# Sensor_Board.net
KiCad netlist of a schematic drawn in EAGLE
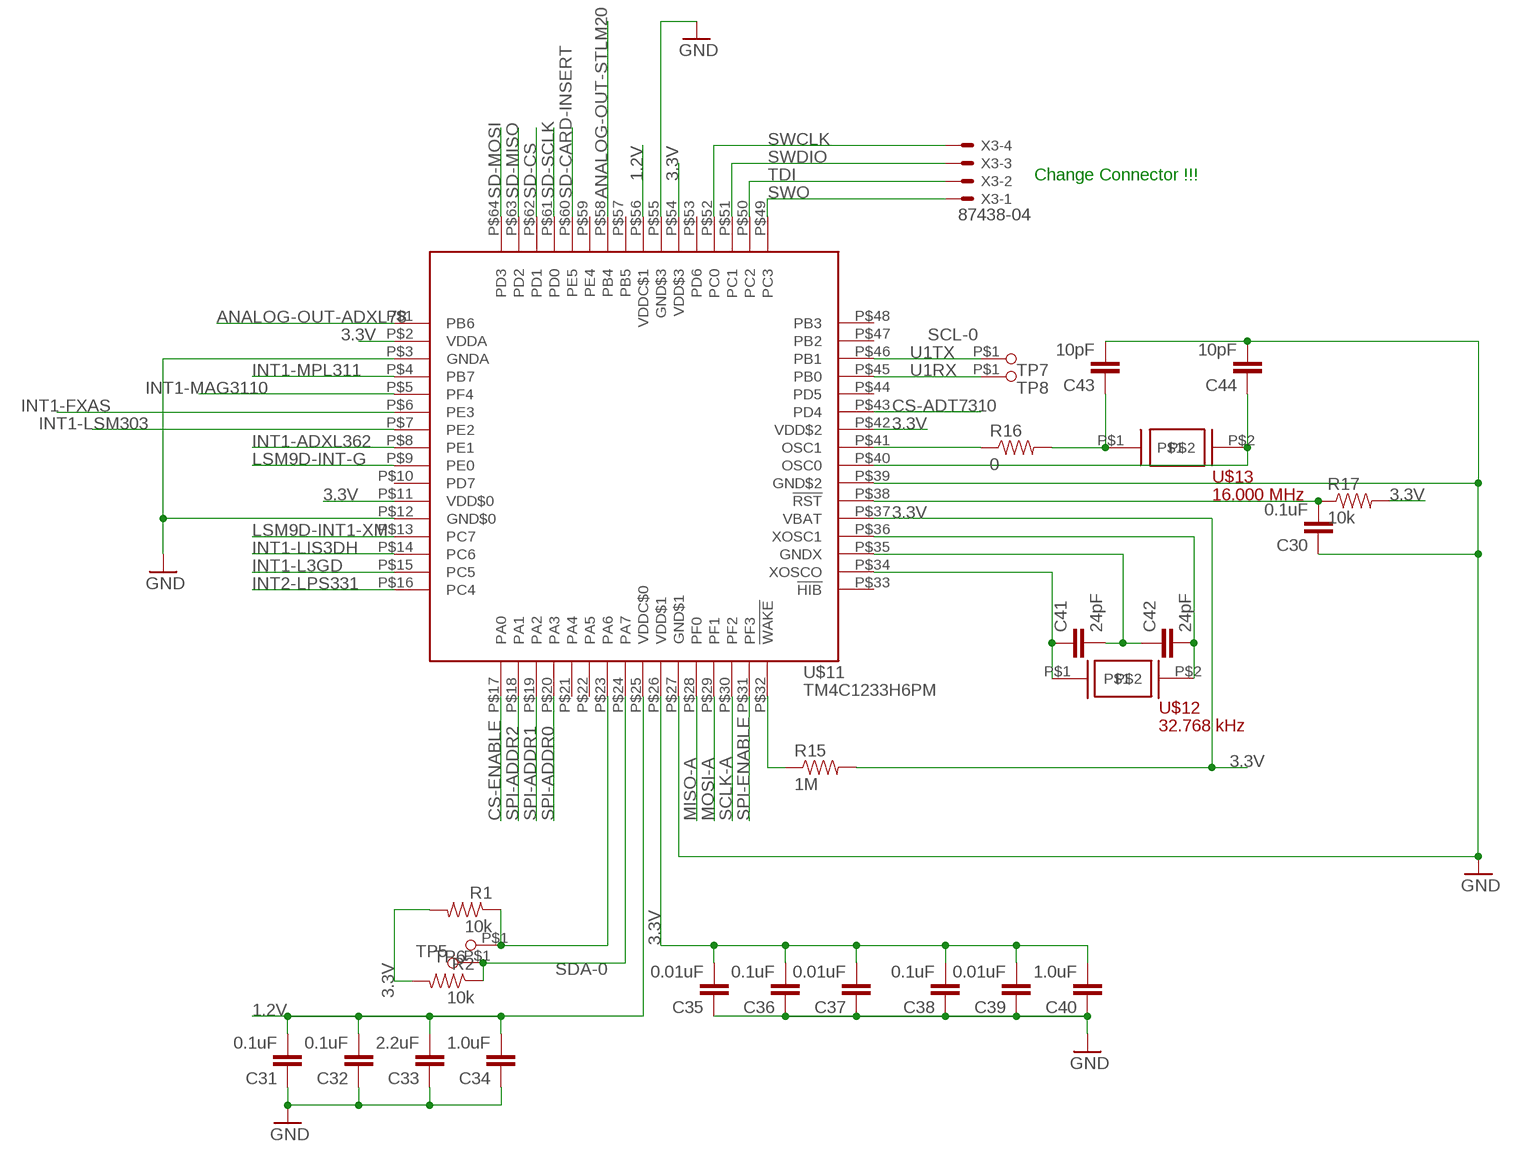
[diagram p0: schematic, sheet 1]
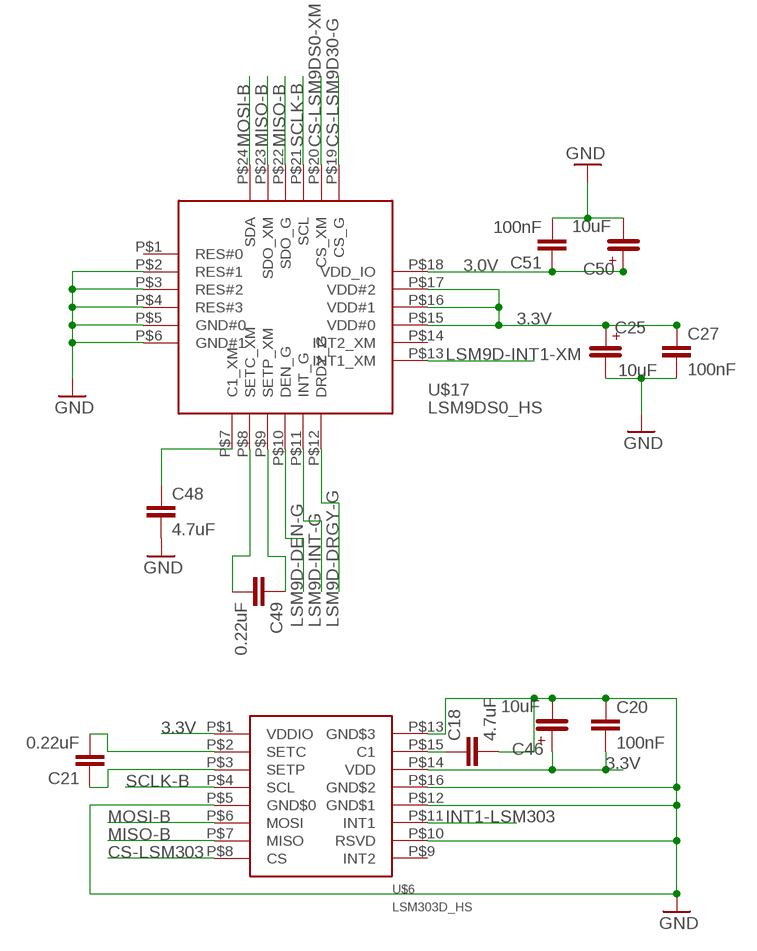
[diagram p1: schematic, sheet 2]
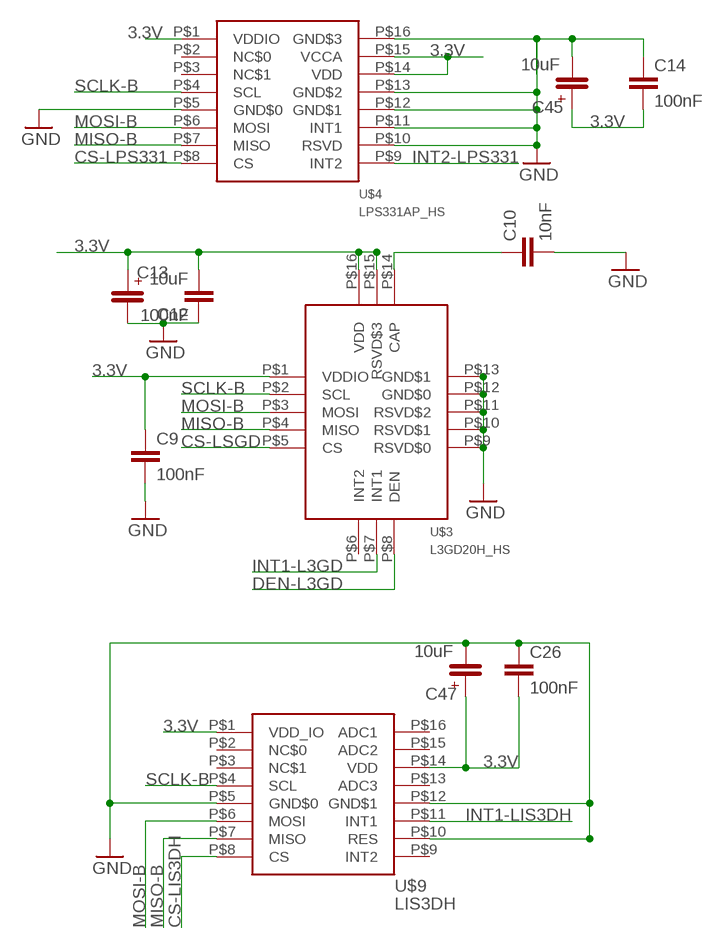
[diagram p2: schematic, sheet 3]
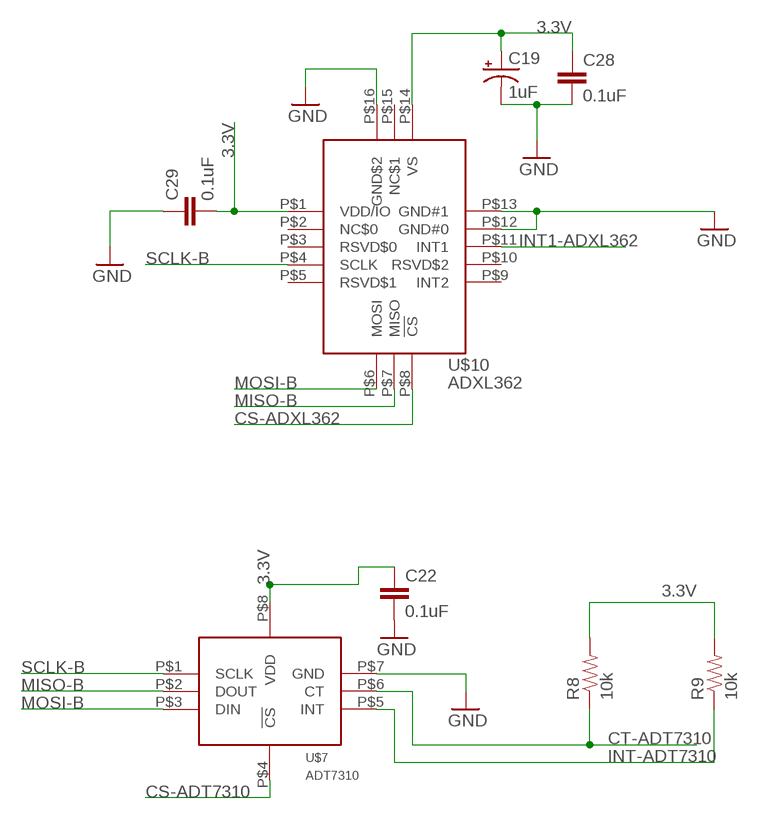
[diagram p3: schematic, sheet 4]
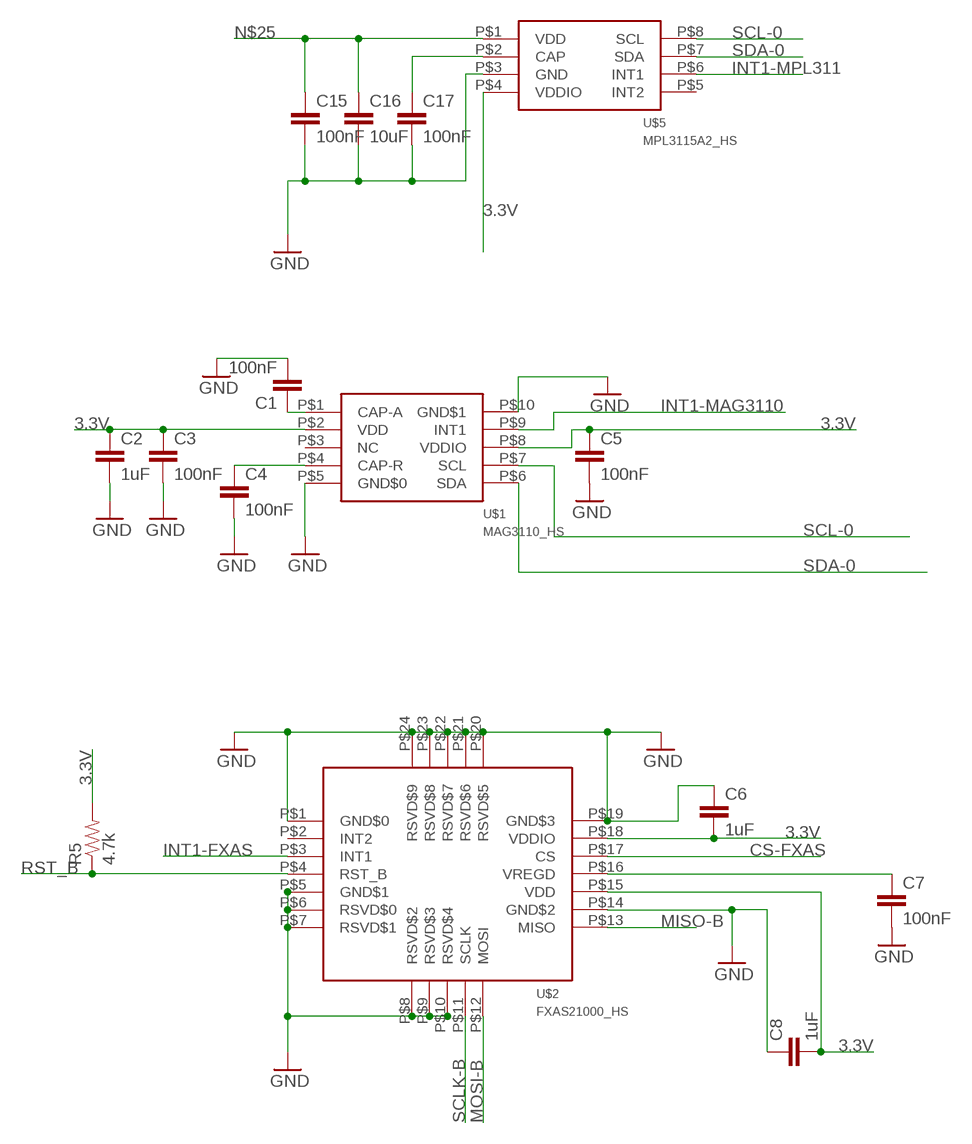
[diagram p4: schematic, sheet 5]
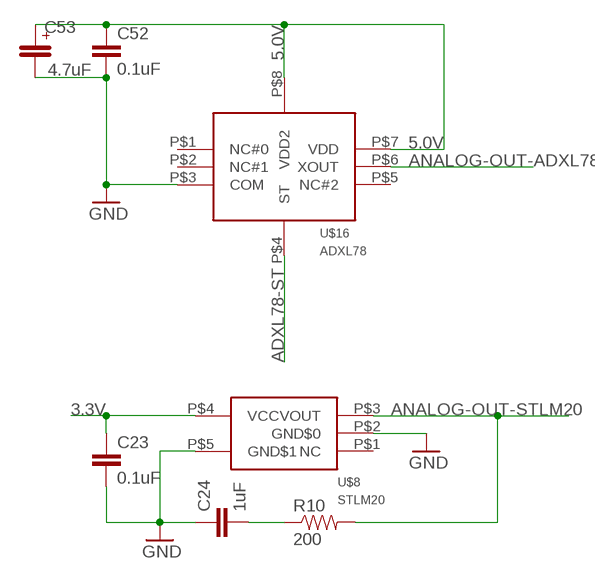
[diagram p5: schematic, sheet 6]
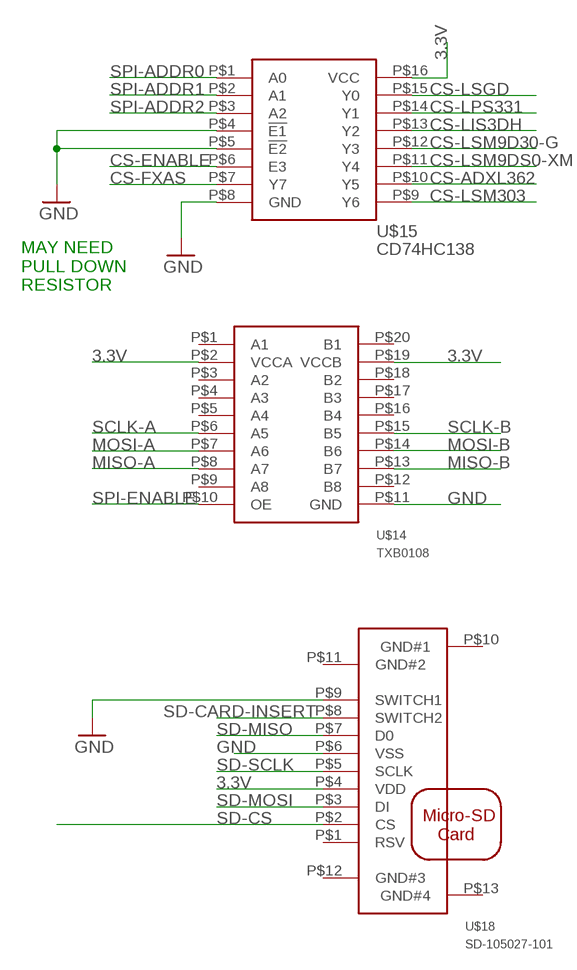
[diagram p6: schematic, sheet 7]
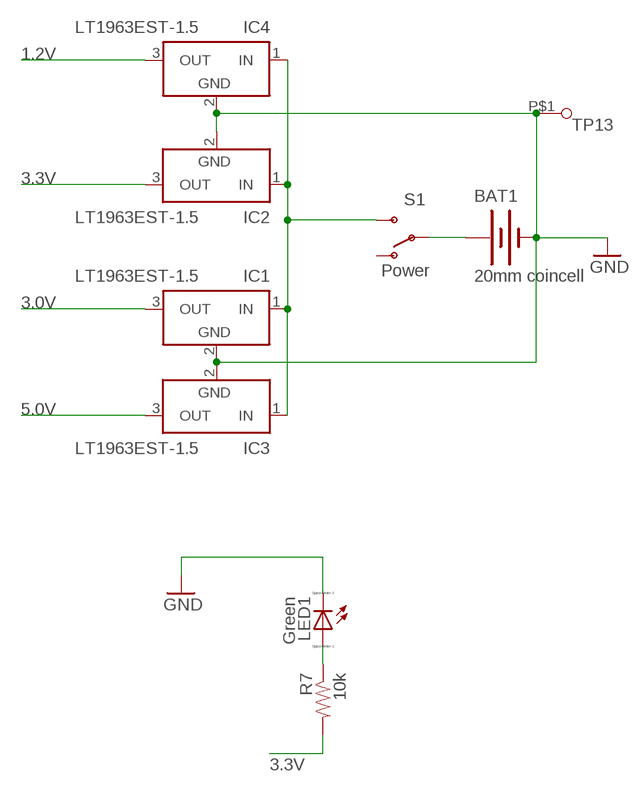
[diagram p7: schematic, sheet 8]

(export (version "E")
  (design (tool "Eeschema 10.0.6"))
  (components
    (comp (ref "C19")
      (value "1uF")
      (footprint "eagle-import:EIA6032")
      (libsource (lib "eagle-import") (part "CAP_POL6032"))
    )
    (comp (ref "C22")
      (value "0.1uF")
      (footprint "eagle-import:0402-CAP")
      (libsource (lib "eagle-import") (part "CAPACITOR"))
    )
    (comp (ref "C28")
      (value "0.1uF")
      (footprint "eagle-import:0402-CAP")
      (libsource (lib "eagle-import") (part "CAPACITOR"))
    )
    (comp (ref "C29")
      (value "0.1uF")
      (footprint "eagle-import:0402-CAP")
      (libsource (lib "eagle-import") (part "CAPACITOR"))
    )
    (comp (ref "R8")
      (value "10k")
      (footprint "eagle-import:0402")
      (libsource (lib "eagle-import") (part "RESISTOR"))
    )
    (comp (ref "R9")
      (value "10k")
      (footprint "eagle-import:0402")
      (libsource (lib "eagle-import") (part "RESISTOR"))
    )
    (comp (ref "U$7")
      (value "ADT7310")
      (footprint "eagle-import:SOIC-8(5X6.2)")
      (libsource (lib "eagle-import") (part "ADT7310"))
    )
    (comp (ref "U$10")
      (value "ADXL362")
      (footprint "eagle-import:LGA-16(3X3.25)_HS")
      (libsource (lib "eagle-import") (part "ADXL362_HS"))
    )
    (comp (ref "C23")
      (value "0.1uF")
      (footprint "eagle-import:0402-CAP")
      (libsource (lib "eagle-import") (part "CAPACITOR"))
    )
    (comp (ref "C24")
      (value "1uF")
      (footprint "eagle-import:0402-CAP")
      (libsource (lib "eagle-import") (part "CAPACITOR"))
    )
    (comp (ref "C52")
      (value "0.1uF")
      (footprint "eagle-import:0402-CAP")
      (libsource (lib "eagle-import") (part "CAPACITOR"))
    )
    (comp (ref "C53")
      (value "4.7uF")
      (footprint "eagle-import:4.3X7.3SMD")
      (libsource (lib "eagle-import") (part "EEFCD0J100ER"))
    )
    (comp (ref "R10")
      (value "200")
      (footprint "eagle-import:0402")
      (libsource (lib "eagle-import") (part "RESISTOR"))
    )
    (comp (ref "U$8")
      (value "STLM20")
      (footprint "eagle-import:SOT323-5L")
      (libsource (lib "eagle-import") (part "STLM20"))
    )
    (comp (ref "U$16")
      (value "ADXL78")
      (footprint "eagle-import:LCC-8(5X5)_HS")
      (libsource (lib "eagle-import") (part "ADXL78"))
    )
    (comp (ref "C30")
      (value "0.1uF")
      (footprint "eagle-import:0402-CAP")
      (libsource (lib "eagle-import") (part "CAPACITOR"))
    )
    (comp (ref "C31")
      (value "0.1uF")
      (footprint "eagle-import:0402-CAP")
      (libsource (lib "eagle-import") (part "CAPACITOR"))
    )
    (comp (ref "C32")
      (value "0.1uF")
      (footprint "eagle-import:0402-CAP")
      (libsource (lib "eagle-import") (part "CAPACITOR"))
    )
    (comp (ref "C33")
      (value "2.2uF")
      (footprint "eagle-import:0402-CAP")
      (libsource (lib "eagle-import") (part "CAPACITOR"))
    )
    (comp (ref "C34")
      (value "1.0uF")
      (footprint "eagle-import:0402-CAP")
      (libsource (lib "eagle-import") (part "CAPACITOR"))
    )
    (comp (ref "C35")
      (value "0.01uF")
      (footprint "eagle-import:0402-CAP")
      (libsource (lib "eagle-import") (part "CAPACITOR"))
    )
    (comp (ref "C36")
      (value "0.1uF")
      (footprint "eagle-import:0402-CAP")
      (libsource (lib "eagle-import") (part "CAPACITOR"))
    )
    (comp (ref "C37")
      (value "0.01uF")
      (footprint "eagle-import:0402-CAP")
      (libsource (lib "eagle-import") (part "CAPACITOR"))
    )
    (comp (ref "C38")
      (value "0.1uF")
      (footprint "eagle-import:0402-CAP")
      (libsource (lib "eagle-import") (part "CAPACITOR"))
    )
    (comp (ref "C39")
      (value "0.01uF")
      (footprint "eagle-import:0402-CAP")
      (libsource (lib "eagle-import") (part "CAPACITOR"))
    )
    (comp (ref "C40")
      (value "1.0uF")
      (footprint "eagle-import:0402-CAP")
      (libsource (lib "eagle-import") (part "CAPACITOR"))
    )
    (comp (ref "C41")
      (value "24pF")
      (footprint "eagle-import:0402-CAP")
      (libsource (lib "eagle-import") (part "CAPACITOR"))
    )
    (comp (ref "C42")
      (value "24pF")
      (footprint "eagle-import:0402-CAP")
      (libsource (lib "eagle-import") (part "CAPACITOR"))
    )
    (comp (ref "C43")
      (value "10pF")
      (footprint "eagle-import:0402-CAP")
      (libsource (lib "eagle-import") (part "CAPACITOR"))
    )
    (comp (ref "C44")
      (value "10pF")
      (footprint "eagle-import:0402-CAP")
      (libsource (lib "eagle-import") (part "CAPACITOR"))
    )
    (comp (ref "R1")
      (value "10k")
      (footprint "eagle-import:0402")
      (libsource (lib "eagle-import") (part "RESISTOR"))
    )
    (comp (ref "R2")
      (value "10k")
      (footprint "eagle-import:0402")
      (libsource (lib "eagle-import") (part "RESISTOR"))
    )
    (comp (ref "R15")
      (value "1M")
      (footprint "eagle-import:0402")
      (libsource (lib "eagle-import") (part "RESISTOR"))
    )
    (comp (ref "R16")
      (value "0")
      (footprint "eagle-import:0402")
      (libsource (lib "eagle-import") (part "RESISTOR"))
    )
    (comp (ref "R17")
      (value "10k")
      (footprint "eagle-import:0402")
      (libsource (lib "eagle-import") (part "RESISTOR"))
    )
    (comp (ref "TP5")
      (value "TESTPAD(ROUND)")
      (footprint "eagle-import:TESTPAD(ROUND)")
      (libsource (lib "eagle-import") (part "TESTPAD(ROUND)"))
    )
    (comp (ref "TP6")
      (value "TESTPAD(ROUND)")
      (footprint "eagle-import:TESTPAD(ROUND)")
      (libsource (lib "eagle-import") (part "TESTPAD(ROUND)"))
    )
    (comp (ref "TP7")
      (value "TESTPAD(ROUND)")
      (footprint "eagle-import:TESTPAD(ROUND)")
      (libsource (lib "eagle-import") (part "TESTPAD(ROUND)"))
    )
    (comp (ref "TP8")
      (value "TESTPAD(ROUND)")
      (footprint "eagle-import:TESTPAD(ROUND)")
      (libsource (lib "eagle-import") (part "TESTPAD(ROUND)"))
    )
    (comp (ref "U$11")
      (value "TM4C1233H6PM")
      (footprint "eagle-import:S-PQFP-G64")
      (libsource (lib "eagle-import") (part "TM4C1233H6PM"))
    )
    (comp (ref "U$12")
      (value "32.768 kHz")
      (footprint "eagle-import:CYLINDRICAL-(1.9DIAX6L)")
      (libsource (lib "eagle-import") (part "AB26TRB"))
    )
    (comp (ref "U$13")
      (value "16.000 MHz")
      (footprint "eagle-import:2-SMD")
      (libsource (lib "eagle-import") (part "NX5032GA"))
    )
    (comp (ref "X3")
      (value "87438-04")
      (footprint "eagle-import:87438-04")
      (libsource (lib "eagle-import") (part "87438-04"))
    )
    (comp (ref "BAT1")
      (value "20mm coincell")
      (footprint "eagle-import:BATTCON_20MM_4LEGS")
      (libsource (lib "eagle-import") (part "BATTERY20MM_4LEGS"))
    )
    (comp (ref "IC1")
      (value "LT1963EST-1.5")
      (footprint "eagle-import:SOT223")
      (libsource (lib "eagle-import") (part "LT1963EST-1.5"))
    )
    (comp (ref "IC2")
      (value "LT1963EST-1.5")
      (footprint "eagle-import:SOT223")
      (libsource (lib "eagle-import") (part "LT1963EST-1.5"))
    )
    (comp (ref "IC3")
      (value "LT1963EST-1.5")
      (footprint "eagle-import:SOT223")
      (libsource (lib "eagle-import") (part "LT1963EST-1.5"))
    )
    (comp (ref "IC4")
      (value "LT1963EST-1.5")
      (footprint "eagle-import:SOT223")
      (libsource (lib "eagle-import") (part "LT1963EST-1.5"))
    )
    (comp (ref "LED1")
      (value "Green")
      (footprint "eagle-import:LED_SML0603")
      (libsource (lib "eagle-import") (part "LED_ESML0603"))
    )
    (comp (ref "R7")
      (value "10k")
      (footprint "eagle-import:0402")
      (libsource (lib "eagle-import") (part "RESISTOR"))
    )
    (comp (ref "S1")
      (value "Power")
      (footprint "eagle-import:SWITCH-SPST-SMD-A")
      (libsource (lib "eagle-import") (part "SWITCH-SPDT-SMD-A"))
    )
    (comp (ref "TP13")
      (value "TESTPAD(ROUND)")
      (footprint "eagle-import:TESTPAD(ROUND)")
      (libsource (lib "eagle-import") (part "TESTPAD(ROUND)"))
    )
    (comp (ref "U$14")
      (value "TXB0108")
      (footprint "eagle-import:TSSOP-(PW)-20")
      (libsource (lib "eagle-import") (part "TXB0108"))
    )
    (comp (ref "U$15")
      (value "CD74HC138")
      (footprint "eagle-import:SOIC-16")
      (libsource (lib "eagle-import") (part "CD74HC138"))
    )
    (comp (ref "U$18")
      (value "SD-105027-101")
      (footprint "eagle-import:SD-105027-101")
      (libsource (lib "eagle-import") (part "SD-105027-101"))
    )
    (comp (ref "C1")
      (value "100nF")
      (footprint "eagle-import:0402-CAP")
      (libsource (lib "eagle-import") (part "CAPACITOR"))
    )
    (comp (ref "C2")
      (value "1uF")
      (footprint "eagle-import:0402-CAP")
      (libsource (lib "eagle-import") (part "CAPACITOR"))
    )
    (comp (ref "C3")
      (value "100nF")
      (footprint "eagle-import:0402-CAP")
      (libsource (lib "eagle-import") (part "CAPACITOR"))
    )
    (comp (ref "C4")
      (value "100nF")
      (footprint "eagle-import:0402-CAP")
      (libsource (lib "eagle-import") (part "CAPACITOR"))
    )
    (comp (ref "C5")
      (value "100nF")
      (footprint "eagle-import:0402-CAP")
      (libsource (lib "eagle-import") (part "CAPACITOR"))
    )
    (comp (ref "C6")
      (value "1uF")
      (footprint "eagle-import:0402-CAP")
      (libsource (lib "eagle-import") (part "CAPACITOR"))
    )
    (comp (ref "C7")
      (value "100nF")
      (footprint "eagle-import:0402-CAP")
      (libsource (lib "eagle-import") (part "CAPACITOR"))
    )
    (comp (ref "C8")
      (value "1uF")
      (footprint "eagle-import:0402-CAP")
      (libsource (lib "eagle-import") (part "CAPACITOR"))
    )
    (comp (ref "C15")
      (value "100nF")
      (footprint "eagle-import:0402-CAP")
      (libsource (lib "eagle-import") (part "CAPACITOR"))
    )
    (comp (ref "C16")
      (value "10uF")
      (footprint "eagle-import:0402-CAP")
      (libsource (lib "eagle-import") (part "CAPACITOR"))
    )
    (comp (ref "C17")
      (value "100nF")
      (footprint "eagle-import:0402-CAP")
      (libsource (lib "eagle-import") (part "CAPACITOR"))
    )
    (comp (ref "R5")
      (value "4.7k")
      (footprint "eagle-import:0402")
      (libsource (lib "eagle-import") (part "RESISTOR"))
    )
    (comp (ref "U$1")
      (value "MAG3110_HS")
      (footprint "eagle-import:DFN-10(2X2)_HS")
      (libsource (lib "eagle-import") (part "MAG3110_HS"))
    )
    (comp (ref "U$2")
      (value "FXAS21000_HS")
      (footprint "eagle-import:QFN-24(4X4)_HS")
      (libsource (lib "eagle-import") (part "FXAS21000_HS"))
    )
    (comp (ref "U$5")
      (value "MPL3115A2_HS")
      (footprint "eagle-import:LGA-8(5X3)_HS")
      (libsource (lib "eagle-import") (part "MPL3115A2_HS"))
    )
    (comp (ref "C18")
      (value "4.7uF")
      (footprint "eagle-import:0402-CAP")
      (libsource (lib "eagle-import") (part "CAPACITOR"))
    )
    (comp (ref "C20")
      (value "100nF")
      (footprint "eagle-import:0402-CAP")
      (libsource (lib "eagle-import") (part "CAPACITOR"))
    )
    (comp (ref "C21")
      (value "0.22uF")
      (footprint "eagle-import:0402-CAP")
      (libsource (lib "eagle-import") (part "CAPACITOR"))
    )
    (comp (ref "C25")
      (value "10uF")
      (footprint "eagle-import:4.3X7.3SMD")
      (libsource (lib "eagle-import") (part "EEFCD0J100ER"))
    )
    (comp (ref "C27")
      (value "100nF")
      (footprint "eagle-import:0402-CAP")
      (libsource (lib "eagle-import") (part "CAPACITOR"))
    )
    (comp (ref "C46")
      (value "10uF")
      (footprint "eagle-import:4.3X7.3SMD")
      (libsource (lib "eagle-import") (part "EEFCD0J100ER"))
    )
    (comp (ref "C48")
      (value "4.7uF")
      (footprint "eagle-import:0402-CAP")
      (libsource (lib "eagle-import") (part "CAPACITOR"))
    )
    (comp (ref "C49")
      (value "0.22uF")
      (footprint "eagle-import:0402-CAP")
      (libsource (lib "eagle-import") (part "CAPACITOR"))
    )
    (comp (ref "C50")
      (value "10uF")
      (footprint "eagle-import:4.3X7.3SMD")
      (libsource (lib "eagle-import") (part "EEFCD0J100ER"))
    )
    (comp (ref "C51")
      (value "100nF")
      (footprint "eagle-import:0402-CAP")
      (libsource (lib "eagle-import") (part "CAPACITOR"))
    )
    (comp (ref "U$6")
      (value "LSM303D_HS")
      (footprint "eagle-import:LGA-16(3X3)_HS")
      (libsource (lib "eagle-import") (part "LSM303D_HS"))
    )
    (comp (ref "U$17")
      (value "LSM9DS0_HS")
      (footprint "eagle-import:LGA-24(4X4)_HS")
      (libsource (lib "eagle-import") (part "LSM9DS0_HS"))
    )
    (comp (ref "C9")
      (value "100nF")
      (footprint "eagle-import:0402-CAP")
      (libsource (lib "eagle-import") (part "CAPACITOR"))
    )
    (comp (ref "C10")
      (value "10nF")
      (footprint "eagle-import:0402-CAP")
      (libsource (lib "eagle-import") (part "CAPACITOR"))
    )
    (comp (ref "C12")
      (value "10uF")
      (footprint "eagle-import:0402-CAP")
      (libsource (lib "eagle-import") (part "CAPACITOR"))
    )
    (comp (ref "C13")
      (value "100nF")
      (footprint "eagle-import:4.3X7.3SMD")
      (libsource (lib "eagle-import") (part "EEFCD0J100ER"))
    )
    (comp (ref "C14")
      (value "100nF")
      (footprint "eagle-import:0402-CAP")
      (libsource (lib "eagle-import") (part "CAPACITOR"))
    )
    (comp (ref "C26")
      (value "100nF")
      (footprint "eagle-import:0402-CAP")
      (libsource (lib "eagle-import") (part "CAPACITOR"))
    )
    (comp (ref "C45")
      (value "10uF")
      (footprint "eagle-import:4.3X7.3SMD")
      (libsource (lib "eagle-import") (part "EEFCD0J100ER"))
    )
    (comp (ref "C47")
      (value "10uF")
      (footprint "eagle-import:4.3X7.3SMD")
      (libsource (lib "eagle-import") (part "EEFCD0J100ER"))
    )
    (comp (ref "U$3")
      (value "L3GD20H_HS")
      (footprint "eagle-import:LGA-16(3X3)_HS")
      (libsource (lib "eagle-import") (part "L3GD20H_HS"))
    )
    (comp (ref "U$4")
      (value "LPS331AP_HS")
      (footprint "eagle-import:LGA-16(3X3)_HS")
      (libsource (lib "eagle-import") (part "LPS331AP_HS"))
    )
    (comp (ref "U$9")
      (value "LIS3DH")
      (footprint "eagle-import:LGA-16(3X3)_HS")
      (libsource (lib "eagle-import") (part "LIS3DH_HS"))
    )
  )
  (nets
    (net (code "1") (name "1.2V") (class "Default")
      (node (ref "C31") (pin "2") (pinfunction "2_2") (pintype "passive"))
      (node (ref "C32") (pin "2") (pinfunction "2_2") (pintype "passive"))
      (node (ref "C33") (pin "2") (pinfunction "2_2") (pintype "passive"))
      (node (ref "C34") (pin "2") (pinfunction "2_2") (pintype "passive"))
      (node (ref "IC4") (pin "3") (pinfunction "OUT_3") (pintype "output"))
      (node (ref "U$11") (pin "P$25") (pinfunction "VDDC$0_P$25") (pintype "bidirectional"))
      (node (ref "U$11") (pin "P$56") (pinfunction "VDDC$1_P$56") (pintype "bidirectional"))
    )
    (net (code "2") (name "3.0V") (class "Default")
      (node (ref "C50") (pin "P$1") (pintype "bidirectional"))
      (node (ref "C51") (pin "1") (pinfunction "1_1") (pintype "passive"))
      (node (ref "IC1") (pin "3") (pinfunction "OUT_3") (pintype "output"))
      (node (ref "U$17") (pin "P$18") (pinfunction "VDD_IO_P$18") (pintype "bidirectional"))
    )
    (net (code "3") (name "3.3V") (class "Default")
      (node (ref "C12") (pin "2") (pinfunction "2_2") (pintype "passive"))
      (node (ref "C13") (pin "P$1") (pintype "bidirectional"))
      (node (ref "C14") (pin "2") (pinfunction "2_2") (pintype "passive"))
      (node (ref "C19") (pin "P$1") (pinfunction "+_P$1") (pintype "passive"))
      (node (ref "C2") (pin "1") (pinfunction "1_1") (pintype "passive"))
      (node (ref "C20") (pin "2") (pinfunction "2_2") (pintype "passive"))
      (node (ref "C22") (pin "1") (pinfunction "1_1") (pintype "passive"))
      (node (ref "C23") (pin "1") (pinfunction "1_1") (pintype "passive"))
      (node (ref "C25") (pin "P$1") (pintype "bidirectional"))
      (node (ref "C26") (pin "2") (pinfunction "2_2") (pintype "passive"))
      (node (ref "C27") (pin "1") (pinfunction "1_1") (pintype "passive"))
      (node (ref "C28") (pin "1") (pinfunction "1_1") (pintype "passive"))
      (node (ref "C29") (pin "2") (pinfunction "2_2") (pintype "passive"))
      (node (ref "C3") (pin "1") (pinfunction "1_1") (pintype "passive"))
      (node (ref "C35") (pin "2") (pinfunction "2_2") (pintype "passive"))
      (node (ref "C36") (pin "2") (pinfunction "2_2") (pintype "passive"))
      (node (ref "C37") (pin "2") (pinfunction "2_2") (pintype "passive"))
      (node (ref "C38") (pin "2") (pinfunction "2_2") (pintype "passive"))
      (node (ref "C39") (pin "2") (pinfunction "2_2") (pintype "passive"))
      (node (ref "C40") (pin "2") (pinfunction "2_2") (pintype "passive"))
      (node (ref "C45") (pin "P$1") (pintype "bidirectional"))
      (node (ref "C46") (pin "P$1") (pintype "bidirectional"))
      (node (ref "C47") (pin "P$1") (pintype "bidirectional"))
      (node (ref "C5") (pin "1") (pinfunction "1_1") (pintype "passive"))
      (node (ref "C6") (pin "2") (pinfunction "2_2") (pintype "passive"))
      (node (ref "C8") (pin "2") (pinfunction "2_2") (pintype "passive"))
      (node (ref "C9") (pin "1") (pinfunction "1_1") (pintype "passive"))
      (node (ref "IC2") (pin "3") (pinfunction "OUT_3") (pintype "output"))
      (node (ref "R1") (pin "2") (pinfunction "2_2") (pintype "passive"))
      (node (ref "R15") (pin "2") (pinfunction "2_2") (pintype "passive"))
      (node (ref "R17") (pin "2") (pinfunction "2_2") (pintype "passive"))
      (node (ref "R2") (pin "2") (pinfunction "2_2") (pintype "passive"))
      (node (ref "R5") (pin "2") (pinfunction "2_2") (pintype "passive"))
      (node (ref "R7") (pin "2") (pinfunction "2_2") (pintype "passive"))
      (node (ref "R8") (pin "2") (pinfunction "2_2") (pintype "passive"))
      (node (ref "R9") (pin "2") (pinfunction "2_2") (pintype "passive"))
      (node (ref "U$1") (pin "P$2") (pinfunction "VDD_P$2") (pintype "bidirectional"))
      (node (ref "U$1") (pin "P$8") (pinfunction "VDDIO_P$8") (pintype "bidirectional"))
      (node (ref "U$10") (pin "P$1") (pinfunction "VDD/IO_P$1") (pintype "bidirectional"))
      (node (ref "U$10") (pin "P$14") (pinfunction "VS_P$14") (pintype "bidirectional"))
      (node (ref "U$11") (pin "P$11") (pinfunction "VDD$0_P$11") (pintype "bidirectional"))
      (node (ref "U$11") (pin "P$2") (pinfunction "VDDA_P$2") (pintype "bidirectional"))
      (node (ref "U$11") (pin "P$26") (pinfunction "VDD$1_P$26") (pintype "bidirectional"))
      (node (ref "U$11") (pin "P$37") (pinfunction "VBAT_P$37") (pintype "bidirectional"))
      (node (ref "U$11") (pin "P$42") (pinfunction "VDD$2_P$42") (pintype "bidirectional"))
      (node (ref "U$11") (pin "P$54") (pinfunction "VDD$3_P$54") (pintype "bidirectional"))
      (node (ref "U$14") (pin "P$19") (pinfunction "VCCB_P$19") (pintype "bidirectional"))
      (node (ref "U$14") (pin "P$2") (pinfunction "VCCA_P$2") (pintype "bidirectional"))
      (node (ref "U$15") (pin "P$16") (pinfunction "VCC_P$16") (pintype "bidirectional"))
      (node (ref "U$17") (pin "P$15") (pinfunction "VDD#0_P$15") (pintype "bidirectional"))
      (node (ref "U$17") (pin "P$16") (pinfunction "VDD#1_P$16") (pintype "bidirectional"))
      (node (ref "U$17") (pin "P$17") (pinfunction "VDD#2_P$17") (pintype "bidirectional"))
      (node (ref "U$18") (pin "P$4") (pinfunction "VDD_P$4") (pintype "bidirectional"))
      (node (ref "U$2") (pin "P$15") (pinfunction "VDD_P$15") (pintype "bidirectional"))
      (node (ref "U$2") (pin "P$18") (pinfunction "VDDIO_P$18") (pintype "bidirectional"))
      (node (ref "U$3") (pin "P$1") (pinfunction "VDDIO_P$1") (pintype "bidirectional"))
      (node (ref "U$3") (pin "P$15") (pinfunction "RSVD$3_P$15") (pintype "bidirectional"))
      (node (ref "U$3") (pin "P$16") (pinfunction "VDD_P$16") (pintype "bidirectional"))
      (node (ref "U$4") (pin "P$1") (pinfunction "VDDIO_P$1") (pintype "bidirectional"))
      (node (ref "U$4") (pin "P$14") (pinfunction "VDD_P$14") (pintype "bidirectional"))
      (node (ref "U$4") (pin "P$15") (pinfunction "VCCA_P$15") (pintype "bidirectional"))
      (node (ref "U$5") (pin "P$4") (pinfunction "VDDIO_P$4") (pintype "bidirectional"))
      (node (ref "U$6") (pin "P$1") (pinfunction "VDDIO_P$1") (pintype "bidirectional"))
      (node (ref "U$6") (pin "P$14") (pinfunction "VDD_P$14") (pintype "bidirectional"))
      (node (ref "U$7") (pin "P$8") (pinfunction "VDD_P$8") (pintype "bidirectional"))
      (node (ref "U$8") (pin "P$4") (pinfunction "VCC_P$4") (pintype "bidirectional"))
      (node (ref "U$9") (pin "P$1") (pinfunction "VDD_IO_P$1") (pintype "bidirectional"))
      (node (ref "U$9") (pin "P$14") (pinfunction "VDD_P$14") (pintype "bidirectional"))
    )
    (net (code "4") (name "5.0V") (class "Default")
      (node (ref "C52") (pin "1") (pinfunction "1_1") (pintype "passive"))
      (node (ref "C53") (pin "P$1") (pintype "bidirectional"))
      (node (ref "IC3") (pin "3") (pinfunction "OUT_3") (pintype "output"))
      (node (ref "U$16") (pin "P$7") (pinfunction "VDD_P$7") (pintype "bidirectional"))
      (node (ref "U$16") (pin "P$8") (pinfunction "VDD2_P$8") (pintype "bidirectional"))
    )
    (net (code "5") (name "ADXL78-ST") (class "Default")
      (node (ref "U$16") (pin "P$4") (pinfunction "ST_P$4") (pintype "bidirectional"))
    )
    (net (code "6") (name "ANALOG-OUT-ADXL78") (class "Default")
      (node (ref "U$11") (pin "P$1") (pinfunction "PB6_P$1") (pintype "bidirectional"))
      (node (ref "U$16") (pin "P$6") (pinfunction "XOUT_P$6") (pintype "bidirectional"))
    )
    (net (code "7") (name "ANALOG-OUT-STLM20") (class "Default")
      (node (ref "R10") (pin "2") (pinfunction "2_2") (pintype "passive"))
      (node (ref "U$11") (pin "P$58") (pinfunction "PB4_P$58") (pintype "bidirectional"))
      (node (ref "U$8") (pin "P$3") (pinfunction "VOUT_P$3") (pintype "bidirectional"))
    )
    (net (code "8") (name "CS-ADT7310") (class "Default")
      (node (ref "U$11") (pin "P$43") (pinfunction "PD4_P$43") (pintype "bidirectional"))
      (node (ref "U$7") (pin "P$4") (pinfunction "~{CS}_P$4") (pintype "bidirectional"))
    )
    (net (code "9") (name "CS-ADXL362") (class "Default")
      (node (ref "U$10") (pin "P$8") (pinfunction "~{CS}_P$8") (pintype "bidirectional"))
      (node (ref "U$15") (pin "P$10") (pinfunction "Y5_P$10") (pintype "bidirectional"))
    )
    (net (code "10") (name "CS-ENABLE") (class "Default")
      (node (ref "U$11") (pin "P$17") (pinfunction "PA0_P$17") (pintype "bidirectional"))
      (node (ref "U$15") (pin "P$6") (pinfunction "E3_P$6") (pintype "bidirectional"))
    )
    (net (code "11") (name "CS-FXAS") (class "Default")
      (node (ref "U$15") (pin "P$7") (pinfunction "Y7_P$7") (pintype "bidirectional"))
      (node (ref "U$2") (pin "P$17") (pinfunction "CS_P$17") (pintype "bidirectional"))
    )
    (net (code "12") (name "CS-LIS3DH") (class "Default")
      (node (ref "U$15") (pin "P$13") (pinfunction "Y2_P$13") (pintype "bidirectional"))
      (node (ref "U$9") (pin "P$8") (pinfunction "CS_P$8") (pintype "bidirectional"))
    )
    (net (code "13") (name "CS-LPS331") (class "Default")
      (node (ref "U$15") (pin "P$14") (pinfunction "Y1_P$14") (pintype "bidirectional"))
      (node (ref "U$4") (pin "P$8") (pinfunction "CS_P$8") (pintype "bidirectional"))
    )
    (net (code "14") (name "CS-LSGD") (class "Default")
      (node (ref "U$15") (pin "P$15") (pinfunction "Y0_P$15") (pintype "bidirectional"))
      (node (ref "U$3") (pin "P$5") (pinfunction "CS_P$5") (pintype "bidirectional"))
    )
    (net (code "15") (name "CS-LSM9D30-G") (class "Default")
      (node (ref "U$15") (pin "P$12") (pinfunction "Y3_P$12") (pintype "bidirectional"))
      (node (ref "U$17") (pin "P$19") (pinfunction "CS_G_P$19") (pintype "bidirectional"))
    )
    (net (code "16") (name "CS-LSM9DS0-XM") (class "Default")
      (node (ref "U$15") (pin "P$11") (pinfunction "Y4_P$11") (pintype "bidirectional"))
      (node (ref "U$17") (pin "P$20") (pinfunction "CS_XM_P$20") (pintype "bidirectional"))
    )
    (net (code "17") (name "CS-LSM303") (class "Default")
      (node (ref "U$15") (pin "P$9") (pinfunction "Y6_P$9") (pintype "bidirectional"))
      (node (ref "U$6") (pin "P$8") (pinfunction "CS_P$8") (pintype "bidirectional"))
    )
    (net (code "18") (name "CT-ADT7310") (class "Default")
      (node (ref "R8") (pin "1") (pinfunction "1_1") (pintype "passive"))
      (node (ref "U$7") (pin "P$6") (pinfunction "CT_P$6") (pintype "bidirectional"))
    )
    (net (code "19") (name "DEN-L3GD") (class "Default")
      (node (ref "U$3") (pin "P$8") (pinfunction "DEN_P$8") (pintype "bidirectional"))
    )
    (net (code "20") (name "GND") (class "Default")
      (node (ref "BAT1") (pin "2") (pinfunction "-_2") (pintype "power_in"))
      (node (ref "C1") (pin "2") (pinfunction "2_2") (pintype "passive"))
      (node (ref "C10") (pin "2") (pinfunction "2_2") (pintype "passive"))
      (node (ref "C12") (pin "1") (pinfunction "1_1") (pintype "passive"))
      (node (ref "C13") (pin "P$2") (pintype "bidirectional"))
      (node (ref "C14") (pin "1") (pinfunction "1_1") (pintype "passive"))
      (node (ref "C15") (pin "2") (pinfunction "2_2") (pintype "passive"))
      (node (ref "C16") (pin "2") (pinfunction "2_2") (pintype "passive"))
      (node (ref "C17") (pin "2") (pinfunction "2_2") (pintype "passive"))
      (node (ref "C18") (pin "2") (pinfunction "2_2") (pintype "passive"))
      (node (ref "C19") (pin "P$2") (pinfunction "-_P$2") (pintype "passive"))
      (node (ref "C2") (pin "2") (pinfunction "2_2") (pintype "passive"))
      (node (ref "C20") (pin "1") (pinfunction "1_1") (pintype "passive"))
      (node (ref "C22") (pin "2") (pinfunction "2_2") (pintype "passive"))
      (node (ref "C23") (pin "2") (pinfunction "2_2") (pintype "passive"))
      (node (ref "C24") (pin "1") (pinfunction "1_1") (pintype "passive"))
      (node (ref "C25") (pin "P$2") (pintype "bidirectional"))
      (node (ref "C26") (pin "1") (pinfunction "1_1") (pintype "passive"))
      (node (ref "C27") (pin "2") (pinfunction "2_2") (pintype "passive"))
      (node (ref "C28") (pin "2") (pinfunction "2_2") (pintype "passive"))
      (node (ref "C29") (pin "1") (pinfunction "1_1") (pintype "passive"))
      (node (ref "C3") (pin "2") (pinfunction "2_2") (pintype "passive"))
      (node (ref "C30") (pin "1") (pinfunction "1_1") (pintype "passive"))
      (node (ref "C31") (pin "1") (pinfunction "1_1") (pintype "passive"))
      (node (ref "C32") (pin "1") (pinfunction "1_1") (pintype "passive"))
      (node (ref "C33") (pin "1") (pinfunction "1_1") (pintype "passive"))
      (node (ref "C34") (pin "1") (pinfunction "1_1") (pintype "passive"))
      (node (ref "C35") (pin "1") (pinfunction "1_1") (pintype "passive"))
      (node (ref "C36") (pin "1") (pinfunction "1_1") (pintype "passive"))
      (node (ref "C37") (pin "1") (pinfunction "1_1") (pintype "passive"))
      (node (ref "C38") (pin "1") (pinfunction "1_1") (pintype "passive"))
      (node (ref "C39") (pin "1") (pinfunction "1_1") (pintype "passive"))
      (node (ref "C4") (pin "2") (pinfunction "2_2") (pintype "passive"))
      (node (ref "C40") (pin "1") (pinfunction "1_1") (pintype "passive"))
      (node (ref "C43") (pin "2") (pinfunction "2_2") (pintype "passive"))
      (node (ref "C44") (pin "2") (pinfunction "2_2") (pintype "passive"))
      (node (ref "C45") (pin "P$2") (pintype "bidirectional"))
      (node (ref "C46") (pin "P$2") (pintype "bidirectional"))
      (node (ref "C47") (pin "P$2") (pintype "bidirectional"))
      (node (ref "C48") (pin "2") (pinfunction "2_2") (pintype "passive"))
      (node (ref "C5") (pin "2") (pinfunction "2_2") (pintype "passive"))
      (node (ref "C50") (pin "P$2") (pintype "bidirectional"))
      (node (ref "C51") (pin "2") (pinfunction "2_2") (pintype "passive"))
      (node (ref "C52") (pin "2") (pinfunction "2_2") (pintype "passive"))
      (node (ref "C53") (pin "P$2") (pintype "bidirectional"))
      (node (ref "C6") (pin "1") (pinfunction "1_1") (pintype "passive"))
      (node (ref "C7") (pin "2") (pinfunction "2_2") (pintype "passive"))
      (node (ref "C8") (pin "1") (pinfunction "1_1") (pintype "passive"))
      (node (ref "C9") (pin "2") (pinfunction "2_2") (pintype "passive"))
      (node (ref "IC1") (pin "2") (pinfunction "GND_2") (pintype "power_in"))
      (node (ref "IC2") (pin "2") (pinfunction "GND_2") (pintype "power_in"))
      (node (ref "IC3") (pin "2") (pinfunction "GND_2") (pintype "power_in"))
      (node (ref "IC4") (pin "2") (pinfunction "GND_2") (pintype "power_in"))
      (node (ref "LED1") (pin "C") (pinfunction "C_C") (pintype "passive"))
      (node (ref "TP13") (pin "P$1") (pinfunction "P$1_P$1") (pintype "bidirectional"))
      (node (ref "U$1") (pin "P$10") (pinfunction "GND$1_P$10") (pintype "bidirectional"))
      (node (ref "U$1") (pin "P$5") (pinfunction "GND$0_P$5") (pintype "bidirectional"))
      (node (ref "U$10") (pin "P$12") (pinfunction "GND#0_P$12") (pintype "bidirectional"))
      (node (ref "U$10") (pin "P$13") (pinfunction "GND#1_P$13") (pintype "bidirectional"))
      (node (ref "U$10") (pin "P$16") (pinfunction "GND$2_P$16") (pintype "bidirectional"))
      (node (ref "U$11") (pin "P$12") (pinfunction "GND$0_P$12") (pintype "bidirectional"))
      (node (ref "U$11") (pin "P$27") (pinfunction "GND$1_P$27") (pintype "bidirectional"))
      (node (ref "U$11") (pin "P$3") (pinfunction "GNDA_P$3") (pintype "bidirectional"))
      (node (ref "U$11") (pin "P$39") (pinfunction "GND$2_P$39") (pintype "bidirectional"))
      (node (ref "U$11") (pin "P$55") (pinfunction "GND$3_P$55") (pintype "bidirectional"))
      (node (ref "U$14") (pin "P$11") (pinfunction "GND_P$11") (pintype "bidirectional"))
      (node (ref "U$15") (pin "P$4") (pinfunction "~{E1}_P$4") (pintype "bidirectional"))
      (node (ref "U$15") (pin "P$5") (pinfunction "~{E2}_P$5") (pintype "bidirectional"))
      (node (ref "U$15") (pin "P$8") (pinfunction "GND_P$8") (pintype "bidirectional"))
      (node (ref "U$16") (pin "P$3") (pinfunction "COM_P$3") (pintype "bidirectional"))
      (node (ref "U$17") (pin "P$2") (pinfunction "RES#1_P$2") (pintype "bidirectional"))
      (node (ref "U$17") (pin "P$3") (pinfunction "RES#2_P$3") (pintype "bidirectional"))
      (node (ref "U$17") (pin "P$4") (pinfunction "RES#3_P$4") (pintype "bidirectional"))
      (node (ref "U$17") (pin "P$5") (pinfunction "GND#0_P$5") (pintype "bidirectional"))
      (node (ref "U$17") (pin "P$6") (pinfunction "GND#1_P$6") (pintype "bidirectional"))
      (node (ref "U$18") (pin "P$6") (pinfunction "VSS_P$6") (pintype "bidirectional"))
      (node (ref "U$18") (pin "P$9") (pinfunction "SWITCH1_P$9") (pintype "bidirectional"))
      (node (ref "U$2") (pin "P$1") (pinfunction "GND$0_P$1") (pintype "bidirectional"))
      (node (ref "U$2") (pin "P$10") (pinfunction "RSVD$4_P$10") (pintype "bidirectional"))
      (node (ref "U$2") (pin "P$14") (pinfunction "GND$2_P$14") (pintype "bidirectional"))
      (node (ref "U$2") (pin "P$19") (pinfunction "GND$3_P$19") (pintype "bidirectional"))
      (node (ref "U$2") (pin "P$20") (pinfunction "RSVD$5_P$20") (pintype "bidirectional"))
      (node (ref "U$2") (pin "P$21") (pinfunction "RSVD$6_P$21") (pintype "bidirectional"))
      (node (ref "U$2") (pin "P$22") (pinfunction "RSVD$7_P$22") (pintype "bidirectional"))
      (node (ref "U$2") (pin "P$23") (pinfunction "RSVD$8_P$23") (pintype "bidirectional"))
      (node (ref "U$2") (pin "P$24") (pinfunction "RSVD$9_P$24") (pintype "bidirectional"))
      (node (ref "U$2") (pin "P$5") (pinfunction "GND$1_P$5") (pintype "bidirectional"))
      (node (ref "U$2") (pin "P$6") (pinfunction "RSVD$0_P$6") (pintype "bidirectional"))
      (node (ref "U$2") (pin "P$7") (pinfunction "RSVD$1_P$7") (pintype "bidirectional"))
      (node (ref "U$2") (pin "P$8") (pinfunction "RSVD$2_P$8") (pintype "bidirectional"))
      (node (ref "U$2") (pin "P$9") (pinfunction "RSVD$3_P$9") (pintype "bidirectional"))
      (node (ref "U$3") (pin "P$10") (pinfunction "RSVD$1_P$10") (pintype "bidirectional"))
      (node (ref "U$3") (pin "P$11") (pinfunction "RSVD$2_P$11") (pintype "bidirectional"))
      (node (ref "U$3") (pin "P$12") (pinfunction "GND$0_P$12") (pintype "bidirectional"))
      (node (ref "U$3") (pin "P$13") (pinfunction "GND$1_P$13") (pintype "bidirectional"))
      (node (ref "U$3") (pin "P$9") (pinfunction "RSVD$0_P$9") (pintype "bidirectional"))
      (node (ref "U$4") (pin "P$10") (pinfunction "RSVD_P$10") (pintype "bidirectional"))
      (node (ref "U$4") (pin "P$11") (pinfunction "INT1_P$11") (pintype "bidirectional"))
      (node (ref "U$4") (pin "P$12") (pinfunction "GND$1_P$12") (pintype "bidirectional"))
      (node (ref "U$4") (pin "P$13") (pinfunction "GND$2_P$13") (pintype "bidirectional"))
      (node (ref "U$4") (pin "P$16") (pinfunction "GND$3_P$16") (pintype "bidirectional"))
      (node (ref "U$4") (pin "P$5") (pinfunction "GND$0_P$5") (pintype "bidirectional"))
      (node (ref "U$5") (pin "P$3") (pinfunction "GND_P$3") (pintype "bidirectional"))
      (node (ref "U$6") (pin "P$10") (pinfunction "RSVD_P$10") (pintype "bidirectional"))
      (node (ref "U$6") (pin "P$12") (pinfunction "GND$1_P$12") (pintype "bidirectional"))
      (node (ref "U$6") (pin "P$13") (pinfunction "GND$3_P$13") (pintype "bidirectional"))
      (node (ref "U$6") (pin "P$16") (pinfunction "GND$2_P$16") (pintype "bidirectional"))
      (node (ref "U$6") (pin "P$5") (pinfunction "GND$0_P$5") (pintype "bidirectional"))
      (node (ref "U$7") (pin "P$7") (pinfunction "GND_P$7") (pintype "bidirectional"))
      (node (ref "U$8") (pin "P$2") (pinfunction "GND$0_P$2") (pintype "bidirectional"))
      (node (ref "U$8") (pin "P$5") (pinfunction "GND$1_P$5") (pintype "bidirectional"))
      (node (ref "U$9") (pin "P$10") (pinfunction "RES_P$10") (pintype "bidirectional"))
      (node (ref "U$9") (pin "P$12") (pinfunction "GND$1_P$12") (pintype "bidirectional"))
      (node (ref "U$9") (pin "P$5") (pinfunction "GND$0_P$5") (pintype "bidirectional"))
    )
    (net (code "21") (name "INT-ADT7310") (class "Default")
      (node (ref "R9") (pin "1") (pinfunction "1_1") (pintype "passive"))
      (node (ref "U$7") (pin "P$5") (pinfunction "INT_P$5") (pintype "bidirectional"))
    )
    (net (code "22") (name "INT1-ADXL362") (class "Default")
      (node (ref "U$10") (pin "P$11") (pinfunction "INT1_P$11") (pintype "bidirectional"))
      (node (ref "U$11") (pin "P$8") (pinfunction "PE1_P$8") (pintype "bidirectional"))
    )
    (net (code "23") (name "INT1-FXAS") (class "Default")
      (node (ref "U$11") (pin "P$6") (pinfunction "PE3_P$6") (pintype "bidirectional"))
      (node (ref "U$2") (pin "P$3") (pinfunction "INT1_P$3") (pintype "bidirectional"))
    )
    (net (code "24") (name "INT1-L3GD") (class "Default")
      (node (ref "U$11") (pin "P$15") (pinfunction "PC5_P$15") (pintype "bidirectional"))
      (node (ref "U$3") (pin "P$7") (pinfunction "INT1_P$7") (pintype "bidirectional"))
    )
    (net (code "25") (name "INT1-LIS3DH") (class "Default")
      (node (ref "U$11") (pin "P$14") (pinfunction "PC6_P$14") (pintype "bidirectional"))
      (node (ref "U$9") (pin "P$11") (pinfunction "INT1_P$11") (pintype "bidirectional"))
    )
    (net (code "26") (name "INT1-LSM303") (class "Default")
      (node (ref "U$11") (pin "P$7") (pinfunction "PE2_P$7") (pintype "bidirectional"))
      (node (ref "U$6") (pin "P$11") (pinfunction "INT1_P$11") (pintype "bidirectional"))
    )
    (net (code "27") (name "INT1-MAG3110") (class "Default")
      (node (ref "U$1") (pin "P$9") (pinfunction "INT1_P$9") (pintype "bidirectional"))
      (node (ref "U$11") (pin "P$5") (pinfunction "PF4_P$5") (pintype "bidirectional"))
    )
    (net (code "28") (name "INT1-MPL311") (class "Default")
      (node (ref "U$11") (pin "P$4") (pinfunction "PB7_P$4") (pintype "bidirectional"))
      (node (ref "U$5") (pin "P$6") (pinfunction "INT1_P$6") (pintype "bidirectional"))
    )
    (net (code "29") (name "INT2-LPS331") (class "Default")
      (node (ref "U$11") (pin "P$16") (pinfunction "PC4_P$16") (pintype "bidirectional"))
      (node (ref "U$4") (pin "P$9") (pinfunction "INT2_P$9") (pintype "bidirectional"))
    )
    (net (code "30") (name "LSM9D-DEN-G") (class "Default")
      (node (ref "U$17") (pin "P$10") (pinfunction "DEN_G_P$10") (pintype "bidirectional"))
    )
    (net (code "31") (name "LSM9D-DRGY-G") (class "Default")
      (node (ref "U$17") (pin "P$12") (pinfunction "DRDY_G_P$12") (pintype "bidirectional"))
    )
    (net (code "32") (name "LSM9D-INT-G") (class "Default")
      (node (ref "U$11") (pin "P$9") (pinfunction "PE0_P$9") (pintype "bidirectional"))
      (node (ref "U$17") (pin "P$11") (pinfunction "INT_G_P$11") (pintype "bidirectional"))
    )
    (net (code "33") (name "LSM9D-INT1-XM") (class "Default")
      (node (ref "U$11") (pin "P$13") (pinfunction "PC7_P$13") (pintype "bidirectional"))
      (node (ref "U$17") (pin "P$13") (pinfunction "INT1_XM_P$13") (pintype "bidirectional"))
    )
    (net (code "34") (name "MISO-A") (class "Default")
      (node (ref "U$11") (pin "P$28") (pinfunction "PF0_P$28") (pintype "bidirectional"))
      (node (ref "U$14") (pin "P$8") (pinfunction "A7_P$8") (pintype "bidirectional"))
    )
    (net (code "35") (name "MISO-B") (class "Default")
      (node (ref "U$10") (pin "P$7") (pinfunction "MISO_P$7") (pintype "bidirectional"))
      (node (ref "U$14") (pin "P$13") (pinfunction "B7_P$13") (pintype "bidirectional"))
      (node (ref "U$17") (pin "P$22") (pinfunction "SDO_G_P$22") (pintype "bidirectional"))
      (node (ref "U$17") (pin "P$23") (pinfunction "SDO_XM_P$23") (pintype "bidirectional"))
      (node (ref "U$2") (pin "P$13") (pinfunction "MISO_P$13") (pintype "bidirectional"))
      (node (ref "U$3") (pin "P$4") (pinfunction "MISO_P$4") (pintype "bidirectional"))
      (node (ref "U$4") (pin "P$7") (pinfunction "MISO_P$7") (pintype "bidirectional"))
      (node (ref "U$6") (pin "P$7") (pinfunction "MISO_P$7") (pintype "bidirectional"))
      (node (ref "U$7") (pin "P$2") (pinfunction "DOUT_P$2") (pintype "bidirectional"))
      (node (ref "U$9") (pin "P$7") (pinfunction "MISO_P$7") (pintype "bidirectional"))
    )
    (net (code "36") (name "MOSI-A") (class "Default")
      (node (ref "U$11") (pin "P$29") (pinfunction "PF1_P$29") (pintype "bidirectional"))
      (node (ref "U$14") (pin "P$7") (pinfunction "A6_P$7") (pintype "bidirectional"))
    )
    (net (code "37") (name "MOSI-B") (class "Default")
      (node (ref "U$10") (pin "P$6") (pinfunction "MOSI_P$6") (pintype "bidirectional"))
      (node (ref "U$14") (pin "P$14") (pinfunction "B6_P$14") (pintype "bidirectional"))
      (node (ref "U$17") (pin "P$24") (pinfunction "SDA_P$24") (pintype "bidirectional"))
      (node (ref "U$2") (pin "P$12") (pinfunction "MOSI_P$12") (pintype "bidirectional"))
      (node (ref "U$3") (pin "P$3") (pinfunction "MOSI_P$3") (pintype "bidirectional"))
      (node (ref "U$4") (pin "P$6") (pinfunction "MOSI_P$6") (pintype "bidirectional"))
      (node (ref "U$6") (pin "P$6") (pinfunction "MOSI_P$6") (pintype "bidirectional"))
      (node (ref "U$7") (pin "P$3") (pinfunction "DIN_P$3") (pintype "bidirectional"))
      (node (ref "U$9") (pin "P$6") (pinfunction "MOSI_P$6") (pintype "bidirectional"))
    )
    (net (code "38") (name "N$25") (class "Default")
      (node (ref "C15") (pin "1") (pinfunction "1_1") (pintype "passive"))
      (node (ref "C16") (pin "1") (pinfunction "1_1") (pintype "passive"))
      (node (ref "U$5") (pin "P$1") (pinfunction "VDD_P$1") (pintype "bidirectional"))
    )
    (net (code "39") (name "Net-(BAT1-+)") (class "Default")
      (node (ref "BAT1") (pin "1") (pinfunction "+_1") (pintype "power_in"))
      (node (ref "S1") (pin "2") (pinfunction "P_2") (pintype "passive"))
    )
    (net (code "40") (name "Net-(C24-Pad2)") (class "Default")
      (node (ref "C24") (pin "2") (pinfunction "2_2") (pintype "passive"))
      (node (ref "R10") (pin "1") (pinfunction "1_1") (pintype "passive"))
    )
    (net (code "41") (name "Net-(C43-Pad1)") (class "Default")
      (node (ref "C43") (pin "1") (pinfunction "1_1") (pintype "passive"))
      (node (ref "R16") (pin "2") (pinfunction "2_2") (pintype "passive"))
      (node (ref "U$13") (pin "P$1") (pinfunction "P$1_P$1") (pintype "bidirectional"))
    )
    (net (code "42") (name "Net-(IC1A-IN)") (class "Default")
      (node (ref "IC1") (pin "1") (pinfunction "IN_1") (pintype "input"))
      (node (ref "IC2") (pin "1") (pinfunction "IN_1") (pintype "input"))
      (node (ref "IC3") (pin "1") (pinfunction "IN_1") (pintype "input"))
      (node (ref "IC4") (pin "1") (pinfunction "IN_1") (pintype "input"))
      (node (ref "S1") (pin "3") (pinfunction "S_3") (pintype "passive"))
    )
    (net (code "43") (name "Net-(LED1-PadA)") (class "Default")
      (node (ref "LED1") (pin "A") (pinfunction "A_A") (pintype "passive"))
      (node (ref "R7") (pin "1") (pinfunction "1_1") (pintype "passive"))
    )
    (net (code "44") (name "Net-(U$1-CAP-A)") (class "Default")
      (node (ref "C1") (pin "1") (pinfunction "1_1") (pintype "passive"))
      (node (ref "U$1") (pin "P$1") (pinfunction "CAP-A_P$1") (pintype "bidirectional"))
    )
    (net (code "45") (name "Net-(U$1-CAP-R)") (class "Default")
      (node (ref "C4") (pin "1") (pinfunction "1_1") (pintype "passive"))
      (node (ref "U$1") (pin "P$4") (pinfunction "CAP-R_P$4") (pintype "bidirectional"))
    )
    (net (code "46") (name "Net-(U$2-VREGD)") (class "Default")
      (node (ref "C7") (pin "1") (pinfunction "1_1") (pintype "passive"))
      (node (ref "U$2") (pin "P$16") (pinfunction "VREGD_P$16") (pintype "bidirectional"))
    )
    (net (code "47") (name "Net-(U$3-CAP)") (class "Default")
      (node (ref "C10") (pin "1") (pinfunction "1_1") (pintype "passive"))
      (node (ref "U$3") (pin "P$14") (pinfunction "CAP_P$14") (pintype "bidirectional"))
    )
    (net (code "48") (name "Net-(U$5-CAP)") (class "Default")
      (node (ref "C17") (pin "1") (pinfunction "1_1") (pintype "passive"))
      (node (ref "U$5") (pin "P$2") (pinfunction "CAP_P$2") (pintype "bidirectional"))
    )
    (net (code "49") (name "Net-(U$6-C1)") (class "Default")
      (node (ref "C18") (pin "1") (pinfunction "1_1") (pintype "passive"))
      (node (ref "U$6") (pin "P$15") (pinfunction "C1_P$15") (pintype "bidirectional"))
    )
    (net (code "50") (name "Net-(U$6-SETC)") (class "Default")
      (node (ref "C21") (pin "2") (pinfunction "2_2") (pintype "passive"))
      (node (ref "U$6") (pin "P$2") (pinfunction "SETC_P$2") (pintype "bidirectional"))
    )
    (net (code "51") (name "Net-(U$6-SETP)") (class "Default")
      (node (ref "C21") (pin "1") (pinfunction "1_1") (pintype "passive"))
      (node (ref "U$6") (pin "P$3") (pinfunction "SETP_P$3") (pintype "bidirectional"))
    )
    (net (code "52") (name "Net-(U$11-GNDX)") (class "Default")
      (node (ref "C41") (pin "2") (pinfunction "2_2") (pintype "passive"))
      (node (ref "C42") (pin "1") (pinfunction "1_1") (pintype "passive"))
      (node (ref "U$11") (pin "P$35") (pinfunction "GNDX_P$35") (pintype "bidirectional"))
    )
    (net (code "53") (name "Net-(U$11-OSC0)") (class "Default")
      (node (ref "C44") (pin "1") (pinfunction "1_1") (pintype "passive"))
      (node (ref "U$11") (pin "P$40") (pinfunction "OSC0_P$40") (pintype "bidirectional"))
      (node (ref "U$13") (pin "P$2") (pinfunction "P$2_P$2") (pintype "bidirectional"))
    )
    (net (code "54") (name "Net-(U$11-OSC1)") (class "Default")
      (node (ref "R16") (pin "1") (pinfunction "1_1") (pintype "passive"))
      (node (ref "U$11") (pin "P$41") (pinfunction "OSC1_P$41") (pintype "bidirectional"))
    )
    (net (code "55") (name "Net-(U$11-XOSC1)") (class "Default")
      (node (ref "C42") (pin "2") (pinfunction "2_2") (pintype "passive"))
      (node (ref "U$11") (pin "P$36") (pinfunction "XOSC1_P$36") (pintype "bidirectional"))
      (node (ref "U$12") (pin "P$2") (pinfunction "P$2_P$2") (pintype "bidirectional"))
    )
    (net (code "56") (name "Net-(U$11-XOSCO)") (class "Default")
      (node (ref "C41") (pin "1") (pinfunction "1_1") (pintype "passive"))
      (node (ref "U$11") (pin "P$34") (pinfunction "XOSCO_P$34") (pintype "bidirectional"))
      (node (ref "U$12") (pin "P$1") (pinfunction "P$1_P$1") (pintype "bidirectional"))
    )
    (net (code "57") (name "Net-(U$11-~{RST})") (class "Default")
      (node (ref "C30") (pin "2") (pinfunction "2_2") (pintype "passive"))
      (node (ref "R17") (pin "1") (pinfunction "1_1") (pintype "passive"))
      (node (ref "U$11") (pin "P$38") (pinfunction "~{RST}_P$38") (pintype "bidirectional"))
    )
    (net (code "58") (name "Net-(U$11-~{WAKE})") (class "Default")
      (node (ref "R15") (pin "1") (pinfunction "1_1") (pintype "passive"))
      (node (ref "U$11") (pin "P$32") (pinfunction "~{WAKE}_P$32") (pintype "bidirectional"))
    )
    (net (code "59") (name "Net-(U$17-C1_XM)") (class "Default")
      (node (ref "C48") (pin "1") (pinfunction "1_1") (pintype "passive"))
      (node (ref "U$17") (pin "P$7") (pinfunction "C1_XM_P$7") (pintype "bidirectional"))
    )
    (net (code "60") (name "Net-(U$17-SETC_XM)") (class "Default")
      (node (ref "C49") (pin "2") (pinfunction "2_2") (pintype "passive"))
      (node (ref "U$17") (pin "P$8") (pinfunction "SETC_XM_P$8") (pintype "bidirectional"))
    )
    (net (code "61") (name "Net-(U$17-SETP_XM)") (class "Default")
      (node (ref "C49") (pin "1") (pinfunction "1_1") (pintype "passive"))
      (node (ref "U$17") (pin "P$9") (pinfunction "SETP_XM_P$9") (pintype "bidirectional"))
    )
    (net (code "62") (name "RST_B") (class "Default")
      (node (ref "R5") (pin "1") (pinfunction "1_1") (pintype "passive"))
      (node (ref "U$2") (pin "P$4") (pinfunction "RST_B_P$4") (pintype "bidirectional"))
    )
    (net (code "63") (name "SCL-0") (class "Default")
      (node (ref "R1") (pin "1") (pinfunction "1_1") (pintype "passive"))
      (node (ref "TP6") (pin "P$1") (pinfunction "P$1_P$1") (pintype "bidirectional"))
      (node (ref "U$1") (pin "P$7") (pinfunction "SCL_P$7") (pintype "bidirectional"))
      (node (ref "U$11") (pin "P$23") (pinfunction "PA6_P$23") (pintype "bidirectional"))
      (node (ref "U$5") (pin "P$8") (pinfunction "SCL_P$8") (pintype "bidirectional"))
    )
    (net (code "64") (name "SCLK-A") (class "Default")
      (node (ref "U$11") (pin "P$30") (pinfunction "PF2_P$30") (pintype "bidirectional"))
      (node (ref "U$14") (pin "P$6") (pinfunction "A5_P$6") (pintype "bidirectional"))
    )
    (net (code "65") (name "SCLK-B") (class "Default")
      (node (ref "U$10") (pin "P$4") (pinfunction "SCLK_P$4") (pintype "bidirectional"))
      (node (ref "U$14") (pin "P$15") (pinfunction "B5_P$15") (pintype "bidirectional"))
      (node (ref "U$17") (pin "P$21") (pinfunction "SCL_P$21") (pintype "bidirectional"))
      (node (ref "U$2") (pin "P$11") (pinfunction "SCLK_P$11") (pintype "bidirectional"))
      (node (ref "U$3") (pin "P$2") (pinfunction "SCL_P$2") (pintype "bidirectional"))
      (node (ref "U$4") (pin "P$4") (pinfunction "SCL_P$4") (pintype "bidirectional"))
      (node (ref "U$6") (pin "P$4") (pinfunction "SCL_P$4") (pintype "bidirectional"))
      (node (ref "U$7") (pin "P$1") (pinfunction "SCLK_P$1") (pintype "bidirectional"))
      (node (ref "U$9") (pin "P$4") (pinfunction "SCL_P$4") (pintype "bidirectional"))
    )
    (net (code "66") (name "SD-CARD-INSERT") (class "Default")
      (node (ref "U$11") (pin "P$60") (pinfunction "PE5_P$60") (pintype "bidirectional"))
      (node (ref "U$18") (pin "P$8") (pinfunction "SWITCH2_P$8") (pintype "bidirectional"))
    )
    (net (code "67") (name "SD-CS") (class "Default")
      (node (ref "U$11") (pin "P$62") (pinfunction "PD1_P$62") (pintype "bidirectional"))
      (node (ref "U$18") (pin "P$2") (pinfunction "CS_P$2") (pintype "bidirectional"))
    )
    (net (code "68") (name "SD-MISO") (class "Default")
      (node (ref "U$11") (pin "P$63") (pinfunction "PD2_P$63") (pintype "bidirectional"))
      (node (ref "U$18") (pin "P$7") (pinfunction "D0_P$7") (pintype "bidirectional"))
    )
    (net (code "69") (name "SD-MOSI") (class "Default")
      (node (ref "U$11") (pin "P$64") (pinfunction "PD3_P$64") (pintype "bidirectional"))
      (node (ref "U$18") (pin "P$3") (pinfunction "DI_P$3") (pintype "bidirectional"))
    )
    (net (code "70") (name "SD-SCLK") (class "Default")
      (node (ref "U$11") (pin "P$61") (pinfunction "PD0_P$61") (pintype "bidirectional"))
      (node (ref "U$18") (pin "P$5") (pinfunction "SCLK_P$5") (pintype "bidirectional"))
    )
    (net (code "71") (name "SDA-0") (class "Default")
      (node (ref "R2") (pin "1") (pinfunction "1_1") (pintype "passive"))
      (node (ref "TP5") (pin "P$1") (pinfunction "P$1_P$1") (pintype "bidirectional"))
      (node (ref "U$1") (pin "P$6") (pinfunction "SDA_P$6") (pintype "bidirectional"))
      (node (ref "U$11") (pin "P$24") (pinfunction "PA7_P$24") (pintype "bidirectional"))
      (node (ref "U$5") (pin "P$7") (pinfunction "SDA_P$7") (pintype "bidirectional"))
    )
    (net (code "72") (name "SPI-ADDR0") (class "Default")
      (node (ref "U$11") (pin "P$20") (pinfunction "PA3_P$20") (pintype "bidirectional"))
      (node (ref "U$15") (pin "P$1") (pinfunction "A0_P$1") (pintype "bidirectional"))
    )
    (net (code "73") (name "SPI-ADDR1") (class "Default")
      (node (ref "U$11") (pin "P$19") (pinfunction "PA2_P$19") (pintype "bidirectional"))
      (node (ref "U$15") (pin "P$2") (pinfunction "A1_P$2") (pintype "bidirectional"))
    )
    (net (code "74") (name "SPI-ADDR2") (class "Default")
      (node (ref "U$11") (pin "P$18") (pinfunction "PA1_P$18") (pintype "bidirectional"))
      (node (ref "U$15") (pin "P$3") (pinfunction "A2_P$3") (pintype "bidirectional"))
    )
    (net (code "75") (name "SPI-ENABLE") (class "Default")
      (node (ref "U$11") (pin "P$31") (pinfunction "PF3_P$31") (pintype "bidirectional"))
      (node (ref "U$14") (pin "P$10") (pinfunction "OE_P$10") (pintype "bidirectional"))
    )
    (net (code "76") (name "SWCLK") (class "Default")
      (node (ref "U$11") (pin "P$52") (pinfunction "PC0_P$52") (pintype "bidirectional"))
      (node (ref "X3") (pin "4") (pinfunction "S_4") (pintype "passive"))
    )
    (net (code "77") (name "SWDIO") (class "Default")
      (node (ref "U$11") (pin "P$51") (pinfunction "PC1_P$51") (pintype "bidirectional"))
      (node (ref "X3") (pin "3") (pinfunction "S_3") (pintype "passive"))
    )
    (net (code "78") (name "SWO") (class "Default")
      (node (ref "U$11") (pin "P$49") (pinfunction "PC3_P$49") (pintype "bidirectional"))
      (node (ref "X3") (pin "1") (pinfunction "S_1") (pintype "passive"))
    )
    (net (code "79") (name "TDI") (class "Default")
      (node (ref "U$11") (pin "P$50") (pinfunction "PC2_P$50") (pintype "bidirectional"))
      (node (ref "X3") (pin "2") (pinfunction "S_2") (pintype "passive"))
    )
    (net (code "80") (name "U1RX") (class "Default")
      (node (ref "TP8") (pin "P$1") (pinfunction "P$1_P$1") (pintype "bidirectional"))
      (node (ref "U$11") (pin "P$45") (pinfunction "PB0_P$45") (pintype "bidirectional"))
    )
    (net (code "81") (name "U1TX") (class "Default")
      (node (ref "TP7") (pin "P$1") (pinfunction "P$1_P$1") (pintype "bidirectional"))
      (node (ref "U$11") (pin "P$46") (pinfunction "PB1_P$46") (pintype "bidirectional"))
    )
    (net (code "82") (name "unconnected-(S1-O-Pad1)") (class "Default")
      (node (ref "S1") (pin "1") (pinfunction "O_1") (pintype "passive"))
    )
    (net (code "83") (name "unconnected-(U$1-NC-PadP$3)") (class "Default")
      (node (ref "U$1") (pin "P$3") (pinfunction "NC_P$3") (pintype "bidirectional"))
    )
    (net (code "84") (name "unconnected-(U$2-INT2-PadP$2)") (class "Default")
      (node (ref "U$2") (pin "P$2") (pinfunction "INT2_P$2") (pintype "bidirectional"))
    )
    (net (code "85") (name "unconnected-(U$3-INT2-PadP$6)") (class "Default")
      (node (ref "U$3") (pin "P$6") (pinfunction "INT2_P$6") (pintype "bidirectional"))
    )
    (net (code "86") (name "unconnected-(U$4-NC$0-PadP$2)") (class "Default")
      (node (ref "U$4") (pin "P$2") (pinfunction "NC$0_P$2") (pintype "bidirectional"))
    )
    (net (code "87") (name "unconnected-(U$4-NC$1-PadP$3)") (class "Default")
      (node (ref "U$4") (pin "P$3") (pinfunction "NC$1_P$3") (pintype "bidirectional"))
    )
    (net (code "88") (name "unconnected-(U$5-INT2-PadP$5)") (class "Default")
      (node (ref "U$5") (pin "P$5") (pinfunction "INT2_P$5") (pintype "bidirectional"))
    )
    (net (code "89") (name "unconnected-(U$6-INT2-PadP$9)") (class "Default")
      (node (ref "U$6") (pin "P$9") (pinfunction "INT2_P$9") (pintype "bidirectional"))
    )
    (net (code "90") (name "unconnected-(U$8-NC-PadP$1)") (class "Default")
      (node (ref "U$8") (pin "P$1") (pinfunction "NC_P$1") (pintype "bidirectional"))
    )
    (net (code "91") (name "unconnected-(U$9-ADC1-PadP$16)") (class "Default")
      (node (ref "U$9") (pin "P$16") (pinfunction "ADC1_P$16") (pintype "bidirectional"))
    )
    (net (code "92") (name "unconnected-(U$9-ADC2-PadP$15)") (class "Default")
      (node (ref "U$9") (pin "P$15") (pinfunction "ADC2_P$15") (pintype "bidirectional"))
    )
    (net (code "93") (name "unconnected-(U$9-ADC3-PadP$13)") (class "Default")
      (node (ref "U$9") (pin "P$13") (pinfunction "ADC3_P$13") (pintype "bidirectional"))
    )
    (net (code "94") (name "unconnected-(U$9-INT2-PadP$9)") (class "Default")
      (node (ref "U$9") (pin "P$9") (pinfunction "INT2_P$9") (pintype "bidirectional"))
    )
    (net (code "95") (name "unconnected-(U$9-NC$0-PadP$2)") (class "Default")
      (node (ref "U$9") (pin "P$2") (pinfunction "NC$0_P$2") (pintype "bidirectional"))
    )
    (net (code "96") (name "unconnected-(U$9-NC$1-PadP$3)") (class "Default")
      (node (ref "U$9") (pin "P$3") (pinfunction "NC$1_P$3") (pintype "bidirectional"))
    )
    (net (code "97") (name "unconnected-(U$10-INT2-PadP$9)") (class "Default")
      (node (ref "U$10") (pin "P$9") (pinfunction "INT2_P$9") (pintype "bidirectional"))
    )
    (net (code "98") (name "unconnected-(U$10-NC$0-PadP$2)") (class "Default")
      (node (ref "U$10") (pin "P$2") (pinfunction "NC$0_P$2") (pintype "bidirectional"))
    )
    (net (code "99") (name "unconnected-(U$10-NC$1-PadP$15)") (class "Default")
      (node (ref "U$10") (pin "P$15") (pinfunction "NC$1_P$15") (pintype "bidirectional"))
    )
    (net (code "100") (name "unconnected-(U$10-RSVD$0-PadP$3)") (class "Default")
      (node (ref "U$10") (pin "P$3") (pinfunction "RSVD$0_P$3") (pintype "bidirectional"))
    )
    (net (code "101") (name "unconnected-(U$10-RSVD$1-PadP$5)") (class "Default")
      (node (ref "U$10") (pin "P$5") (pinfunction "RSVD$1_P$5") (pintype "bidirectional"))
    )
    (net (code "102") (name "unconnected-(U$10-RSVD$2-PadP$10)") (class "Default")
      (node (ref "U$10") (pin "P$10") (pinfunction "RSVD$2_P$10") (pintype "bidirectional"))
    )
    (net (code "103") (name "unconnected-(U$11-PA4-PadP$21)") (class "Default")
      (node (ref "U$11") (pin "P$21") (pinfunction "PA4_P$21") (pintype "bidirectional"))
    )
    (net (code "104") (name "unconnected-(U$11-PA5-PadP$22)") (class "Default")
      (node (ref "U$11") (pin "P$22") (pinfunction "PA5_P$22") (pintype "bidirectional"))
    )
    (net (code "105") (name "unconnected-(U$11-PB2-PadP$47)") (class "Default")
      (node (ref "U$11") (pin "P$47") (pinfunction "PB2_P$47") (pintype "bidirectional"))
    )
    (net (code "106") (name "unconnected-(U$11-PB3-PadP$48)") (class "Default")
      (node (ref "U$11") (pin "P$48") (pinfunction "PB3_P$48") (pintype "bidirectional"))
    )
    (net (code "107") (name "unconnected-(U$11-PB5-PadP$57)") (class "Default")
      (node (ref "U$11") (pin "P$57") (pinfunction "PB5_P$57") (pintype "bidirectional"))
    )
    (net (code "108") (name "unconnected-(U$11-PD5-PadP$44)") (class "Default")
      (node (ref "U$11") (pin "P$44") (pinfunction "PD5_P$44") (pintype "bidirectional"))
    )
    (net (code "109") (name "unconnected-(U$11-PD6-PadP$53)") (class "Default")
      (node (ref "U$11") (pin "P$53") (pinfunction "PD6_P$53") (pintype "bidirectional"))
    )
    (net (code "110") (name "unconnected-(U$11-PD7-PadP$10)") (class "Default")
      (node (ref "U$11") (pin "P$10") (pinfunction "PD7_P$10") (pintype "bidirectional"))
    )
    (net (code "111") (name "unconnected-(U$11-PE4-PadP$59)") (class "Default")
      (node (ref "U$11") (pin "P$59") (pinfunction "PE4_P$59") (pintype "bidirectional"))
    )
    (net (code "112") (name "unconnected-(U$11-~{HIB}-PadP$33)") (class "Default")
      (node (ref "U$11") (pin "P$33") (pinfunction "~{HIB}_P$33") (pintype "bidirectional"))
    )
    (net (code "113") (name "unconnected-(U$14-A1-PadP$1)") (class "Default")
      (node (ref "U$14") (pin "P$1") (pinfunction "A1_P$1") (pintype "bidirectional"))
    )
    (net (code "114") (name "unconnected-(U$14-A2-PadP$3)") (class "Default")
      (node (ref "U$14") (pin "P$3") (pinfunction "A2_P$3") (pintype "bidirectional"))
    )
    (net (code "115") (name "unconnected-(U$14-A3-PadP$4)") (class "Default")
      (node (ref "U$14") (pin "P$4") (pinfunction "A3_P$4") (pintype "bidirectional"))
    )
    (net (code "116") (name "unconnected-(U$14-A4-PadP$5)") (class "Default")
      (node (ref "U$14") (pin "P$5") (pinfunction "A4_P$5") (pintype "bidirectional"))
    )
    (net (code "117") (name "unconnected-(U$14-A8-PadP$9)") (class "Default")
      (node (ref "U$14") (pin "P$9") (pinfunction "A8_P$9") (pintype "bidirectional"))
    )
    (net (code "118") (name "unconnected-(U$14-B1-PadP$20)") (class "Default")
      (node (ref "U$14") (pin "P$20") (pinfunction "B1_P$20") (pintype "bidirectional"))
    )
    (net (code "119") (name "unconnected-(U$14-B2-PadP$18)") (class "Default")
      (node (ref "U$14") (pin "P$18") (pinfunction "B2_P$18") (pintype "bidirectional"))
    )
    (net (code "120") (name "unconnected-(U$14-B3-PadP$17)") (class "Default")
      (node (ref "U$14") (pin "P$17") (pinfunction "B3_P$17") (pintype "bidirectional"))
    )
    (net (code "121") (name "unconnected-(U$14-B4-PadP$16)") (class "Default")
      (node (ref "U$14") (pin "P$16") (pinfunction "B4_P$16") (pintype "bidirectional"))
    )
    (net (code "122") (name "unconnected-(U$14-B8-PadP$12)") (class "Default")
      (node (ref "U$14") (pin "P$12") (pinfunction "B8_P$12") (pintype "bidirectional"))
    )
    (net (code "123") (name "unconnected-(U$16-NC#0-PadP$1)") (class "Default")
      (node (ref "U$16") (pin "P$1") (pinfunction "NC#0_P$1") (pintype "bidirectional"))
    )
    (net (code "124") (name "unconnected-(U$16-NC#1-PadP$2)") (class "Default")
      (node (ref "U$16") (pin "P$2") (pinfunction "NC#1_P$2") (pintype "bidirectional"))
    )
    (net (code "125") (name "unconnected-(U$16-NC#2-PadP$5)") (class "Default")
      (node (ref "U$16") (pin "P$5") (pinfunction "NC#2_P$5") (pintype "bidirectional"))
    )
    (net (code "126") (name "unconnected-(U$17-INT2_XM-PadP$14)") (class "Default")
      (node (ref "U$17") (pin "P$14") (pinfunction "INT2_XM_P$14") (pintype "bidirectional"))
    )
    (net (code "127") (name "unconnected-(U$17-RES#0-PadP$1)") (class "Default")
      (node (ref "U$17") (pin "P$1") (pinfunction "RES#0_P$1") (pintype "bidirectional"))
    )
    (net (code "128") (name "unconnected-(U$18-GND#1-PadP$10)") (class "Default")
      (node (ref "U$18") (pin "P$10") (pinfunction "GND#1_P$10") (pintype "bidirectional"))
    )
    (net (code "129") (name "unconnected-(U$18-GND#2-PadP$11)") (class "Default")
      (node (ref "U$18") (pin "P$11") (pinfunction "GND#2_P$11") (pintype "bidirectional"))
    )
    (net (code "130") (name "unconnected-(U$18-GND#3-PadP$12)") (class "Default")
      (node (ref "U$18") (pin "P$12") (pinfunction "GND#3_P$12") (pintype "bidirectional"))
    )
    (net (code "131") (name "unconnected-(U$18-GND#4-PadP$13)") (class "Default")
      (node (ref "U$18") (pin "P$13") (pinfunction "GND#4_P$13") (pintype "bidirectional"))
    )
    (net (code "132") (name "unconnected-(U$18-RSV-PadP$1)") (class "Default")
      (node (ref "U$18") (pin "P$1") (pinfunction "RSV_P$1") (pintype "bidirectional"))
    )
  )
)
